# MotorControl.net
KiCad netlist of a schematic drawn in Altium Designer
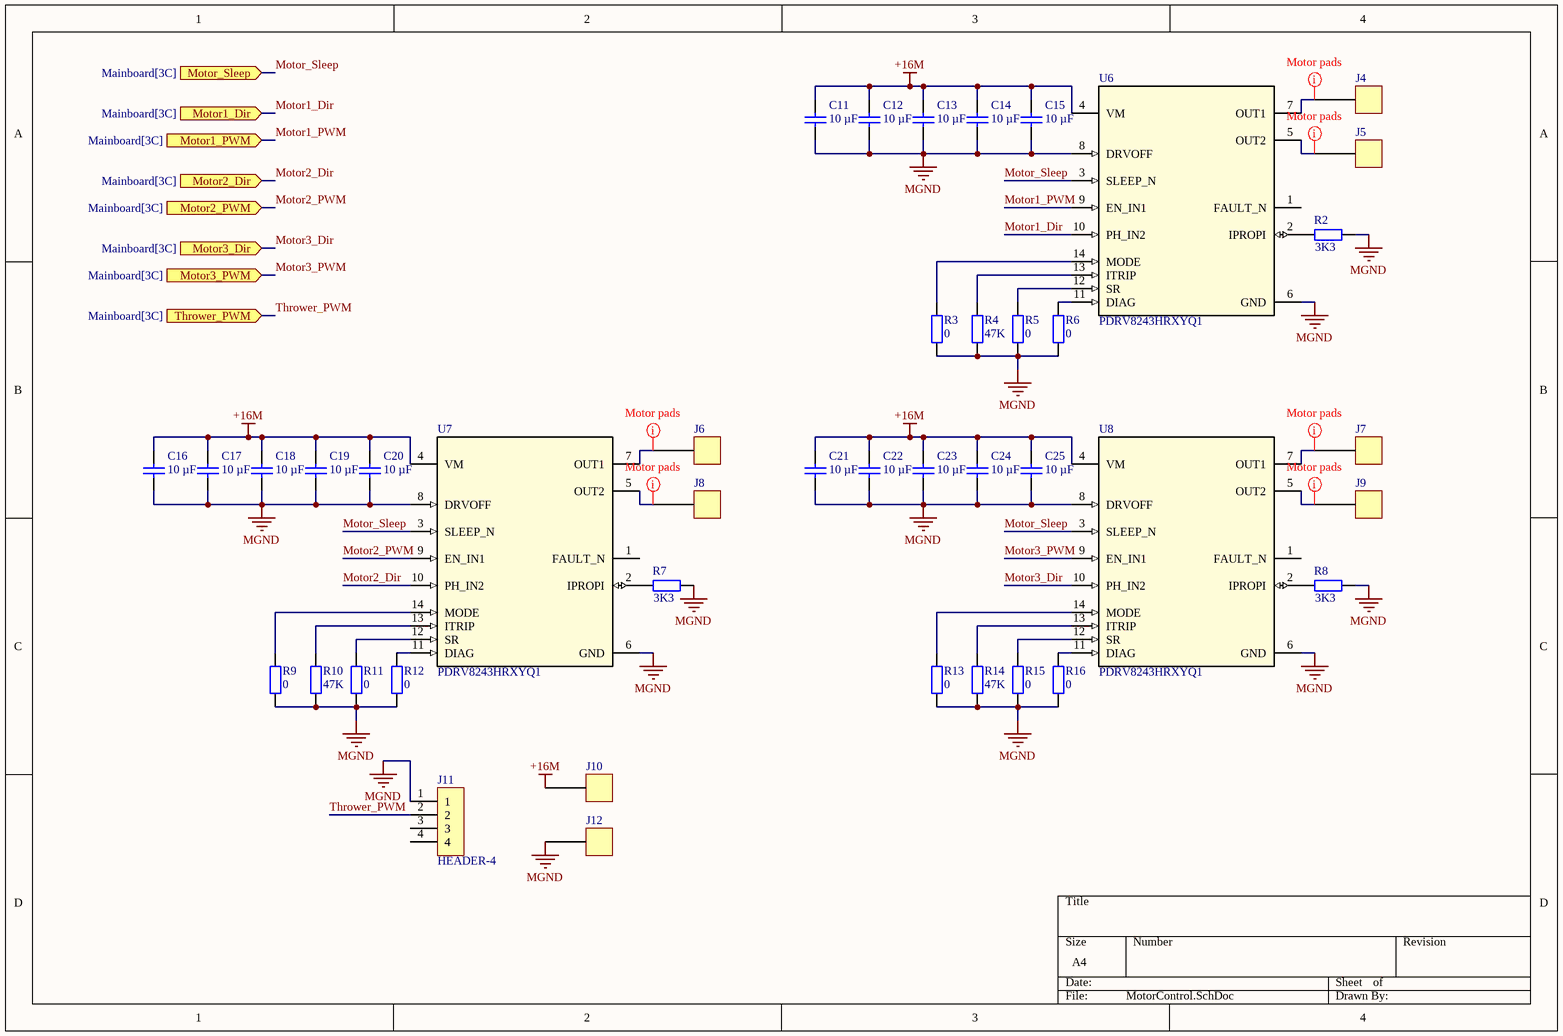
[diagram p0: MotorControl.SchDoc]

(export (version "E")
  (design (tool "Eeschema 10.0.6"))
  (components
    (comp (ref "C11")
      (value "10 µF")
      (footprint "CAP_0805")
      (description "Multilayer Ceramic Capacitors")
      (fields (field (name "TOLERANCE") "10%") (field (name "Comment") "MLCC"))
      (libsource (lib "Tartu University") (part "MLCC"))
    )
    (comp (ref "C12")
      (value "10 µF")
      (footprint "CAP_0805")
      (description "Multilayer Ceramic Capacitors")
      (fields (field (name "TOLERANCE") "10%") (field (name "Comment") "MLCC"))
      (libsource (lib "Tartu University") (part "MLCC"))
    )
    (comp (ref "C13")
      (value "10 µF")
      (footprint "CAP_0805")
      (description "Multilayer Ceramic Capacitors")
      (fields (field (name "TOLERANCE") "10%") (field (name "Comment") "MLCC"))
      (libsource (lib "Tartu University") (part "MLCC"))
    )
    (comp (ref "C14")
      (value "10 µF")
      (footprint "CAP_0805")
      (description "Multilayer Ceramic Capacitors")
      (fields (field (name "TOLERANCE") "10%") (field (name "Comment") "MLCC"))
      (libsource (lib "Tartu University") (part "MLCC"))
    )
    (comp (ref "C15")
      (value "10 µF")
      (footprint "CAP_0805")
      (description "Multilayer Ceramic Capacitors")
      (fields (field (name "TOLERANCE") "10%") (field (name "Comment") "MLCC"))
      (libsource (lib "Tartu University") (part "MLCC"))
    )
    (comp (ref "C16")
      (value "10 µF")
      (footprint "CAP_0805")
      (description "Multilayer Ceramic Capacitors")
      (fields (field (name "TOLERANCE") "10%") (field (name "Comment") "MLCC"))
      (libsource (lib "Tartu University") (part "MLCC"))
    )
    (comp (ref "C17")
      (value "10 µF")
      (footprint "CAP_0805")
      (description "Multilayer Ceramic Capacitors")
      (fields (field (name "TOLERANCE") "10%") (field (name "Comment") "MLCC"))
      (libsource (lib "Tartu University") (part "MLCC"))
    )
    (comp (ref "C18")
      (value "10 µF")
      (footprint "CAP_0805")
      (description "Multilayer Ceramic Capacitors")
      (fields (field (name "TOLERANCE") "10%") (field (name "Comment") "MLCC"))
      (libsource (lib "Tartu University") (part "MLCC"))
    )
    (comp (ref "C19")
      (value "10 µF")
      (footprint "CAP_0805")
      (description "Multilayer Ceramic Capacitors")
      (fields (field (name "TOLERANCE") "10%") (field (name "Comment") "MLCC"))
      (libsource (lib "Tartu University") (part "MLCC"))
    )
    (comp (ref "C20")
      (value "10 µF")
      (footprint "CAP_0805")
      (description "Multilayer Ceramic Capacitors")
      (fields (field (name "TOLERANCE") "10%") (field (name "Comment") "MLCC"))
      (libsource (lib "Tartu University") (part "MLCC"))
    )
    (comp (ref "C21")
      (value "10 µF")
      (footprint "CAP_0805")
      (description "Multilayer Ceramic Capacitors")
      (fields (field (name "TOLERANCE") "10%") (field (name "Comment") "MLCC"))
      (libsource (lib "Tartu University") (part "MLCC"))
    )
    (comp (ref "C22")
      (value "10 µF")
      (footprint "CAP_0805")
      (description "Multilayer Ceramic Capacitors")
      (fields (field (name "TOLERANCE") "10%") (field (name "Comment") "MLCC"))
      (libsource (lib "Tartu University") (part "MLCC"))
    )
    (comp (ref "C23")
      (value "10 µF")
      (footprint "CAP_0805")
      (description "Multilayer Ceramic Capacitors")
      (fields (field (name "TOLERANCE") "10%") (field (name "Comment") "MLCC"))
      (libsource (lib "Tartu University") (part "MLCC"))
    )
    (comp (ref "C24")
      (value "10 µF")
      (footprint "CAP_0805")
      (description "Multilayer Ceramic Capacitors")
      (fields (field (name "TOLERANCE") "10%") (field (name "Comment") "MLCC"))
      (libsource (lib "Tartu University") (part "MLCC"))
    )
    (comp (ref "C25")
      (value "10 µF")
      (footprint "CAP_0805")
      (description "Multilayer Ceramic Capacitors")
      (fields (field (name "TOLERANCE") "10%") (field (name "Comment") "MLCC"))
      (libsource (lib "Tartu University") (part "MLCC"))
    )
    (comp (ref "J4")
      (value "Generic Power Pad")
      (footprint "New footprint 1")
      (libsource (lib "Tartu University") (part "Power Pad"))
    )
    (comp (ref "J5")
      (value "Generic Power Pad")
      (footprint "New footprint 1")
      (libsource (lib "Tartu University") (part "Power Pad"))
    )
    (comp (ref "J6")
      (value "Generic Power Pad")
      (footprint "New footprint 1")
      (libsource (lib "Tartu University") (part "Power Pad"))
    )
    (comp (ref "J7")
      (value "Generic Power Pad")
      (footprint "New footprint 1")
      (libsource (lib "Tartu University") (part "Power Pad"))
    )
    (comp (ref "J8")
      (value "Generic Power Pad")
      (footprint "New footprint 1")
      (libsource (lib "Tartu University") (part "Power Pad"))
    )
    (comp (ref "J9")
      (value "Generic Power Pad")
      (footprint "New footprint 1")
      (libsource (lib "Tartu University") (part "Power Pad"))
    )
    (comp (ref "J10")
      (value "Generic Power Pad")
      (footprint "New footprint 1")
      (libsource (lib "Tartu University") (part "Power Pad"))
    )
    (comp (ref "J11")
      (value "HEADER-4")
      (footprint "MICRO-MATCH-FOB-04")
      (fields (field (name "SOURCE") "connectors_micromatch.SchLib"))
      (libsource (lib "Tartu University") (part "HEADER-4"))
    )
    (comp (ref "J12")
      (value "Generic Power Pad")
      (footprint "New footprint 1")
      (libsource (lib "Tartu University") (part "Power Pad"))
    )
    (comp (ref "R2")
      (value "3K3")
      (footprint "RC0603N")
      (description "Chip Resistors")
      (fields (field (name "Comment") "RES"))
      (libsource (lib "Tartu University") (part "MELF"))
    )
    (comp (ref "R3")
      (value "0")
      (footprint "RC0603N")
      (description "Chip Resistors")
      (fields (field (name "Comment") "RES"))
      (libsource (lib "Tartu University") (part "MELF"))
    )
    (comp (ref "R4")
      (value "47K")
      (footprint "RC0603N")
      (description "Chip Resistors")
      (fields (field (name "Comment") "RES"))
      (libsource (lib "Tartu University") (part "MELF"))
    )
    (comp (ref "R5")
      (value "0")
      (footprint "RC0603N")
      (description "Chip Resistors")
      (fields (field (name "Comment") "RES"))
      (libsource (lib "Tartu University") (part "MELF"))
    )
    (comp (ref "R6")
      (value "0")
      (footprint "RC0603N")
      (description "Chip Resistors")
      (fields (field (name "Comment") "RES"))
      (libsource (lib "Tartu University") (part "MELF"))
    )
    (comp (ref "R7")
      (value "3K3")
      (footprint "RC0603N")
      (description "Chip Resistors")
      (fields (field (name "Comment") "RES"))
      (libsource (lib "Tartu University") (part "MELF"))
    )
    (comp (ref "R8")
      (value "3K3")
      (footprint "RC0603N")
      (description "Chip Resistors")
      (fields (field (name "Comment") "RES"))
      (libsource (lib "Tartu University") (part "MELF"))
    )
    (comp (ref "R9")
      (value "0")
      (footprint "RC0603N")
      (description "Chip Resistors")
      (fields (field (name "Comment") "RES"))
      (libsource (lib "Tartu University") (part "MELF"))
    )
    (comp (ref "R10")
      (value "47K")
      (footprint "RC0603N")
      (description "Chip Resistors")
      (fields (field (name "Comment") "RES"))
      (libsource (lib "Tartu University") (part "MELF"))
    )
    (comp (ref "R11")
      (value "0")
      (footprint "RC0603N")
      (description "Chip Resistors")
      (fields (field (name "Comment") "RES"))
      (libsource (lib "Tartu University") (part "MELF"))
    )
    (comp (ref "R12")
      (value "0")
      (footprint "RC0603N")
      (description "Chip Resistors")
      (fields (field (name "Comment") "RES"))
      (libsource (lib "Tartu University") (part "MELF"))
    )
    (comp (ref "R13")
      (value "0")
      (footprint "RC0603N")
      (description "Chip Resistors")
      (fields (field (name "Comment") "RES"))
      (libsource (lib "Tartu University") (part "MELF"))
    )
    (comp (ref "R14")
      (value "47K")
      (footprint "RC0603N")
      (description "Chip Resistors")
      (fields (field (name "Comment") "RES"))
      (libsource (lib "Tartu University") (part "MELF"))
    )
    (comp (ref "R15")
      (value "0")
      (footprint "RC0603N")
      (description "Chip Resistors")
      (fields (field (name "Comment") "RES"))
      (libsource (lib "Tartu University") (part "MELF"))
    )
    (comp (ref "R16")
      (value "0")
      (footprint "RC0603N")
      (description "Chip Resistors")
      (fields (field (name "Comment") "RES"))
      (libsource (lib "Tartu University") (part "MELF"))
    )
    (comp (ref "U6")
      (value "PDRV8243HRXYQ1")
      (footprint "RXY0014A-MFG")
      (description "No Description Available")
      (fields (field (name "COPYRIGHT") "Copyright (C) 2022 Ultra Librarian. All rights reserved."))
      (libsource (lib "Tartu University") (part "PDRV8243HRXYQ1"))
    )
    (comp (ref "U7")
      (value "PDRV8243HRXYQ1")
      (footprint "RXY0014A-MFG")
      (description "No Description Available")
      (fields (field (name "COPYRIGHT") "Copyright (C) 2022 Ultra Librarian. All rights reserved."))
      (libsource (lib "Tartu University") (part "PDRV8243HRXYQ1"))
    )
    (comp (ref "U8")
      (value "PDRV8243HRXYQ1")
      (footprint "RXY0014A-MFG")
      (description "No Description Available")
      (fields (field (name "COPYRIGHT") "Copyright (C) 2022 Ultra Librarian. All rights reserved."))
      (libsource (lib "Tartu University") (part "PDRV8243HRXYQ1"))
    )
  )
  (nets
    (net (code "1") (name "+16M") (class "Default")
      (node (ref "C11") (pin "2") (pinfunction "2_2") (pintype "passive"))
      (node (ref "C12") (pin "2") (pinfunction "2_2") (pintype "passive"))
      (node (ref "C13") (pin "2") (pinfunction "2_2") (pintype "passive"))
      (node (ref "C14") (pin "2") (pinfunction "2_2") (pintype "passive"))
      (node (ref "C15") (pin "2") (pinfunction "2_2") (pintype "passive"))
      (node (ref "C16") (pin "2") (pinfunction "2_2") (pintype "passive"))
      (node (ref "C17") (pin "2") (pinfunction "2_2") (pintype "passive"))
      (node (ref "C18") (pin "2") (pinfunction "2_2") (pintype "passive"))
      (node (ref "C19") (pin "2") (pinfunction "2_2") (pintype "passive"))
      (node (ref "C20") (pin "2") (pinfunction "2_2") (pintype "passive"))
      (node (ref "C21") (pin "2") (pinfunction "2_2") (pintype "passive"))
      (node (ref "C22") (pin "2") (pinfunction "2_2") (pintype "passive"))
      (node (ref "C23") (pin "2") (pinfunction "2_2") (pintype "passive"))
      (node (ref "C24") (pin "2") (pinfunction "2_2") (pintype "passive"))
      (node (ref "C25") (pin "2") (pinfunction "2_2") (pintype "passive"))
      (node (ref "J10") (pin "1") (pinfunction "1_1") (pintype "passive"))
      (node (ref "U6") (pin "4") (pinfunction "VM_4") (pintype "power_in"))
      (node (ref "U7") (pin "4") (pinfunction "VM_4") (pintype "power_in"))
      (node (ref "U8") (pin "4") (pinfunction "VM_4") (pintype "power_in"))
    )
    (net (code "2") (name "/Motor1_Dir") (class "Default")
      (node (ref "U6") (pin "10") (pinfunction "PH_IN2_10") (pintype "input"))
    )
    (net (code "3") (name "/Motor1_PWM") (class "Default")
      (node (ref "U6") (pin "9") (pinfunction "EN_IN1_9") (pintype "input"))
    )
    (net (code "4") (name "/Motor2_Dir") (class "Default")
      (node (ref "U7") (pin "10") (pinfunction "PH_IN2_10") (pintype "input"))
    )
    (net (code "5") (name "/Motor2_PWM") (class "Default")
      (node (ref "U7") (pin "9") (pinfunction "EN_IN1_9") (pintype "input"))
    )
    (net (code "6") (name "/Motor3_Dir") (class "Default")
      (node (ref "U8") (pin "10") (pinfunction "PH_IN2_10") (pintype "input"))
    )
    (net (code "7") (name "/Motor3_PWM") (class "Default")
      (node (ref "U8") (pin "9") (pinfunction "EN_IN1_9") (pintype "input"))
    )
    (net (code "8") (name "/Motor_Sleep") (class "Default")
      (node (ref "U6") (pin "3") (pinfunction "SLEEP_N_3") (pintype "input"))
      (node (ref "U7") (pin "3") (pinfunction "SLEEP_N_3") (pintype "input"))
      (node (ref "U8") (pin "3") (pinfunction "SLEEP_N_3") (pintype "input"))
    )
    (net (code "9") (name "/Thrower_PWM") (class "Default")
      (node (ref "J11") (pin "2") (pinfunction "2_2") (pintype "passive"))
    )
    (net (code "10") (name "MGND") (class "Default")
      (node (ref "C11") (pin "1") (pinfunction "1_1") (pintype "passive"))
      (node (ref "C12") (pin "1") (pinfunction "1_1") (pintype "passive"))
      (node (ref "C13") (pin "1") (pinfunction "1_1") (pintype "passive"))
      (node (ref "C14") (pin "1") (pinfunction "1_1") (pintype "passive"))
      (node (ref "C15") (pin "1") (pinfunction "1_1") (pintype "passive"))
      (node (ref "C16") (pin "1") (pinfunction "1_1") (pintype "passive"))
      (node (ref "C17") (pin "1") (pinfunction "1_1") (pintype "passive"))
      (node (ref "C18") (pin "1") (pinfunction "1_1") (pintype "passive"))
      (node (ref "C19") (pin "1") (pinfunction "1_1") (pintype "passive"))
      (node (ref "C20") (pin "1") (pinfunction "1_1") (pintype "passive"))
      (node (ref "C21") (pin "1") (pinfunction "1_1") (pintype "passive"))
      (node (ref "C22") (pin "1") (pinfunction "1_1") (pintype "passive"))
      (node (ref "C23") (pin "1") (pinfunction "1_1") (pintype "passive"))
      (node (ref "C24") (pin "1") (pinfunction "1_1") (pintype "passive"))
      (node (ref "C25") (pin "1") (pinfunction "1_1") (pintype "passive"))
      (node (ref "J11") (pin "1") (pinfunction "1_1") (pintype "passive"))
      (node (ref "J12") (pin "1") (pinfunction "1_1") (pintype "passive"))
      (node (ref "R10") (pin "1") (pinfunction "1_1") (pintype "passive"))
      (node (ref "R11") (pin "1") (pinfunction "1_1") (pintype "passive"))
      (node (ref "R12") (pin "1") (pinfunction "1_1") (pintype "passive"))
      (node (ref "R13") (pin "1") (pinfunction "1_1") (pintype "passive"))
      (node (ref "R14") (pin "1") (pinfunction "1_1") (pintype "passive"))
      (node (ref "R15") (pin "1") (pinfunction "1_1") (pintype "passive"))
      (node (ref "R16") (pin "1") (pinfunction "1_1") (pintype "passive"))
      (node (ref "R2") (pin "2") (pinfunction "2_2") (pintype "passive"))
      (node (ref "R3") (pin "1") (pinfunction "1_1") (pintype "passive"))
      (node (ref "R4") (pin "1") (pinfunction "1_1") (pintype "passive"))
      (node (ref "R5") (pin "1") (pinfunction "1_1") (pintype "passive"))
      (node (ref "R6") (pin "1") (pinfunction "1_1") (pintype "passive"))
      (node (ref "R7") (pin "2") (pinfunction "2_2") (pintype "passive"))
      (node (ref "R8") (pin "2") (pinfunction "2_2") (pintype "passive"))
      (node (ref "R9") (pin "1") (pinfunction "1_1") (pintype "passive"))
      (node (ref "U6") (pin "6") (pinfunction "GND_6") (pintype "power_in"))
      (node (ref "U6") (pin "8") (pinfunction "DRVOFF_8") (pintype "input"))
      (node (ref "U7") (pin "6") (pinfunction "GND_6") (pintype "power_in"))
      (node (ref "U7") (pin "8") (pinfunction "DRVOFF_8") (pintype "input"))
      (node (ref "U8") (pin "6") (pinfunction "GND_6") (pintype "power_in"))
      (node (ref "U8") (pin "8") (pinfunction "DRVOFF_8") (pintype "input"))
    )
    (net (code "11") (name "Net-(U6-DIAG)") (class "Default")
      (node (ref "R6") (pin "2") (pinfunction "2_2") (pintype "passive"))
      (node (ref "U6") (pin "11") (pinfunction "DIAG_11") (pintype "input"))
    )
    (net (code "12") (name "Net-(U6-IPROPI)") (class "Default")
      (node (ref "R2") (pin "1") (pinfunction "1_1") (pintype "passive"))
      (node (ref "U6") (pin "2") (pinfunction "IPROPI_2") (pintype "bidirectional"))
    )
    (net (code "13") (name "Net-(U6-ITRIP)") (class "Default")
      (node (ref "R4") (pin "2") (pinfunction "2_2") (pintype "passive"))
      (node (ref "U6") (pin "13") (pinfunction "ITRIP_13") (pintype "input"))
    )
    (net (code "14") (name "Net-(U6-MODE)") (class "Default")
      (node (ref "R3") (pin "2") (pinfunction "2_2") (pintype "passive"))
      (node (ref "U6") (pin "14") (pinfunction "MODE_14") (pintype "input"))
    )
    (net (code "15") (name "Net-(U6-OUT1)") (class "Default")
      (node (ref "J4") (pin "1") (pinfunction "1_1") (pintype "passive"))
      (node (ref "U6") (pin "7") (pinfunction "OUT1_7") (pintype "passive"))
    )
    (net (code "16") (name "Net-(U6-OUT2)") (class "Default")
      (node (ref "J5") (pin "1") (pinfunction "1_1") (pintype "passive"))
      (node (ref "U6") (pin "5") (pinfunction "OUT2_5") (pintype "passive"))
    )
    (net (code "17") (name "Net-(U6-SR)") (class "Default")
      (node (ref "R5") (pin "2") (pinfunction "2_2") (pintype "passive"))
      (node (ref "U6") (pin "12") (pinfunction "SR_12") (pintype "input"))
    )
    (net (code "18") (name "Net-(U7-DIAG)") (class "Default")
      (node (ref "R12") (pin "2") (pinfunction "2_2") (pintype "passive"))
      (node (ref "U7") (pin "11") (pinfunction "DIAG_11") (pintype "input"))
    )
    (net (code "19") (name "Net-(U7-IPROPI)") (class "Default")
      (node (ref "R7") (pin "1") (pinfunction "1_1") (pintype "passive"))
      (node (ref "U7") (pin "2") (pinfunction "IPROPI_2") (pintype "bidirectional"))
    )
    (net (code "20") (name "Net-(U7-ITRIP)") (class "Default")
      (node (ref "R10") (pin "2") (pinfunction "2_2") (pintype "passive"))
      (node (ref "U7") (pin "13") (pinfunction "ITRIP_13") (pintype "input"))
    )
    (net (code "21") (name "Net-(U7-MODE)") (class "Default")
      (node (ref "R9") (pin "2") (pinfunction "2_2") (pintype "passive"))
      (node (ref "U7") (pin "14") (pinfunction "MODE_14") (pintype "input"))
    )
    (net (code "22") (name "Net-(U7-OUT1)") (class "Default")
      (node (ref "J6") (pin "1") (pinfunction "1_1") (pintype "passive"))
      (node (ref "U7") (pin "7") (pinfunction "OUT1_7") (pintype "passive"))
    )
    (net (code "23") (name "Net-(U7-OUT2)") (class "Default")
      (node (ref "J8") (pin "1") (pinfunction "1_1") (pintype "passive"))
      (node (ref "U7") (pin "5") (pinfunction "OUT2_5") (pintype "passive"))
    )
    (net (code "24") (name "Net-(U7-SR)") (class "Default")
      (node (ref "R11") (pin "2") (pinfunction "2_2") (pintype "passive"))
      (node (ref "U7") (pin "12") (pinfunction "SR_12") (pintype "input"))
    )
    (net (code "25") (name "Net-(U8-DIAG)") (class "Default")
      (node (ref "R16") (pin "2") (pinfunction "2_2") (pintype "passive"))
      (node (ref "U8") (pin "11") (pinfunction "DIAG_11") (pintype "input"))
    )
    (net (code "26") (name "Net-(U8-IPROPI)") (class "Default")
      (node (ref "R8") (pin "1") (pinfunction "1_1") (pintype "passive"))
      (node (ref "U8") (pin "2") (pinfunction "IPROPI_2") (pintype "bidirectional"))
    )
    (net (code "27") (name "Net-(U8-ITRIP)") (class "Default")
      (node (ref "R14") (pin "2") (pinfunction "2_2") (pintype "passive"))
      (node (ref "U8") (pin "13") (pinfunction "ITRIP_13") (pintype "input"))
    )
    (net (code "28") (name "Net-(U8-MODE)") (class "Default")
      (node (ref "R13") (pin "2") (pinfunction "2_2") (pintype "passive"))
      (node (ref "U8") (pin "14") (pinfunction "MODE_14") (pintype "input"))
    )
    (net (code "29") (name "Net-(U8-OUT1)") (class "Default")
      (node (ref "J7") (pin "1") (pinfunction "1_1") (pintype "passive"))
      (node (ref "U8") (pin "7") (pinfunction "OUT1_7") (pintype "passive"))
    )
    (net (code "30") (name "Net-(U8-OUT2)") (class "Default")
      (node (ref "J9") (pin "1") (pinfunction "1_1") (pintype "passive"))
      (node (ref "U8") (pin "5") (pinfunction "OUT2_5") (pintype "passive"))
    )
    (net (code "31") (name "Net-(U8-SR)") (class "Default")
      (node (ref "R15") (pin "2") (pinfunction "2_2") (pintype "passive"))
      (node (ref "U8") (pin "12") (pinfunction "SR_12") (pintype "input"))
    )
    (net (code "32") (name "unconnected-(J11-Pad3)") (class "Default")
      (node (ref "J11") (pin "3") (pinfunction "3_3") (pintype "passive"))
    )
    (net (code "33") (name "unconnected-(J11-Pad4)") (class "Default")
      (node (ref "J11") (pin "4") (pinfunction "4_4") (pintype "passive"))
    )
    (net (code "34") (name "unconnected-(U6-FAULT_N-Pad1)") (class "Default")
      (node (ref "U6") (pin "1") (pinfunction "FAULT_N_1") (pintype "open_collector"))
    )
    (net (code "35") (name "unconnected-(U7-FAULT_N-Pad1)") (class "Default")
      (node (ref "U7") (pin "1") (pinfunction "FAULT_N_1") (pintype "open_collector"))
    )
    (net (code "36") (name "unconnected-(U8-FAULT_N-Pad1)") (class "Default")
      (node (ref "U8") (pin "1") (pinfunction "FAULT_N_1") (pintype "open_collector"))
    )
  )
)
